# PCB_Curso_Octubre.net
KiCad netlist of a schematic drawn in Altium Designer
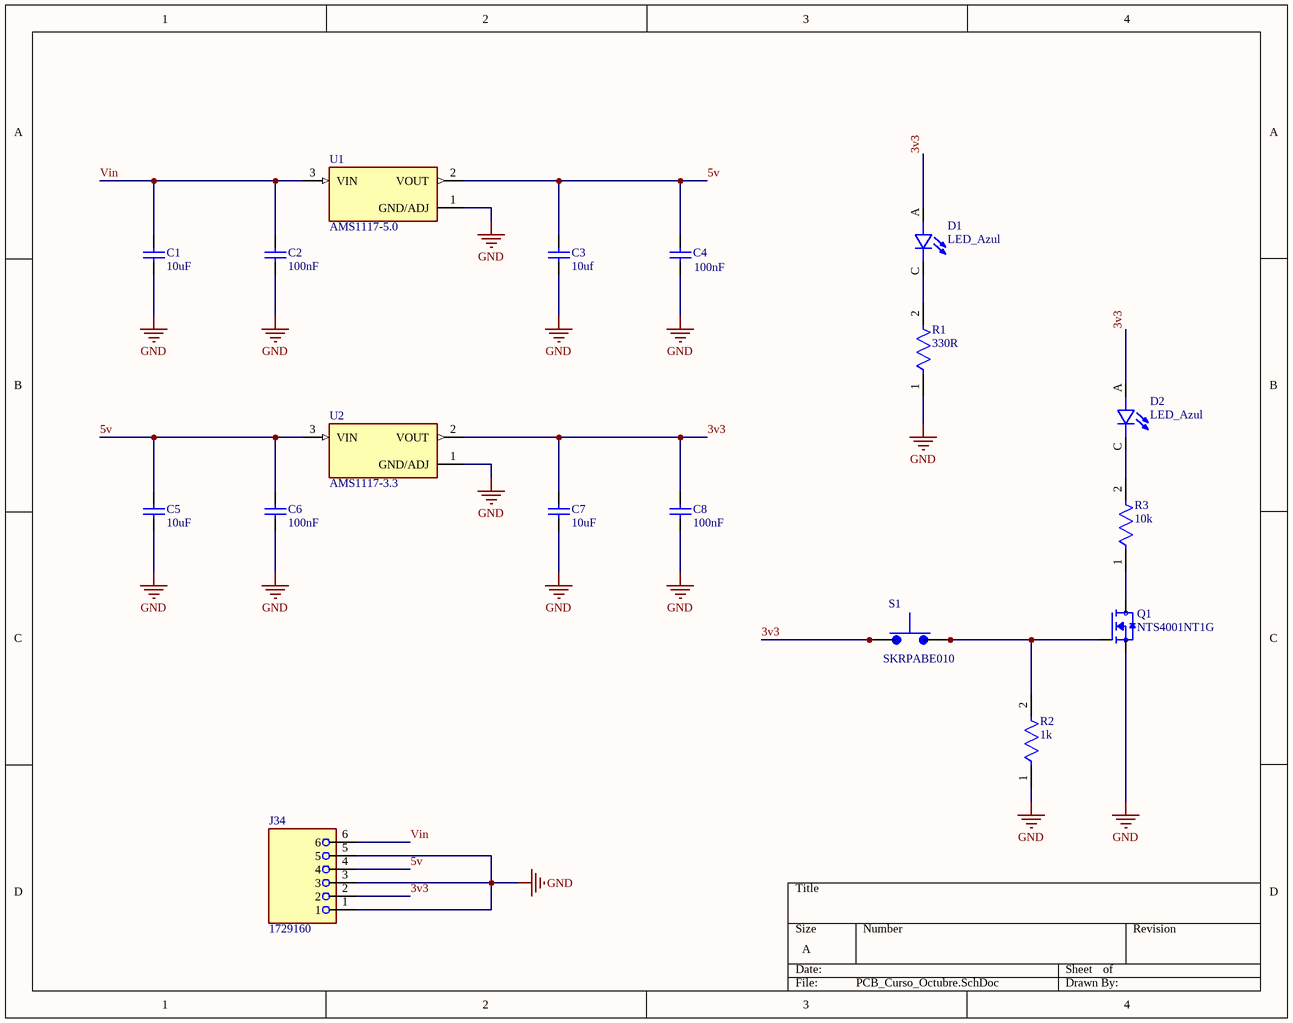
[diagram p0: PCB_Curso_Octubre.SchDoc]

(export (version "E")
  (design (tool "Eeschema 10.0.6"))
  (components
    (comp (ref "C1")
      (value "10uF")
      (footprint "CAPC2013X145X48ML20T23")
      (fields (field (name "MANUFACTURER") "Vitramon") (field (name "PART NUMBER") "VJ0805Y682KXAMT"))
      (libsource (lib "Altium Content Vault") (part "CAP"))
    )
    (comp (ref "C2")
      (value "100nF")
      (footprint "CAPC2013X145X48ML20T23")
      (fields (field (name "MANUFACTURER") "Vitramon") (field (name "PART NUMBER") "VJ0805Y682KXAMT"))
      (libsource (lib "Altium Content Vault") (part "CAP"))
    )
    (comp (ref "C3")
      (value "10uf")
      (footprint "CAPC2013X145X48ML20T23")
      (fields (field (name "MANUFACTURER") "Vitramon") (field (name "PART NUMBER") "VJ0805Y682KXAMT"))
      (libsource (lib "Altium Content Vault") (part "CAP"))
    )
    (comp (ref "C4")
      (value "100nF")
      (footprint "CAPC2013X145X48ML20T23")
      (fields (field (name "MANUFACTURER") "Vitramon") (field (name "PART NUMBER") "VJ0805Y682KXAMT"))
      (libsource (lib "Altium Content Vault") (part "CAP"))
    )
    (comp (ref "C5")
      (value "10uF")
      (footprint "CAPC2013X145X48ML20T23")
      (fields (field (name "MANUFACTURER") "Vitramon") (field (name "PART NUMBER") "VJ0805Y682KXAMT"))
      (libsource (lib "Altium Content Vault") (part "CAP"))
    )
    (comp (ref "C6")
      (value "100nF")
      (footprint "CAPC2013X145X48ML20T23")
      (fields (field (name "MANUFACTURER") "Vitramon") (field (name "PART NUMBER") "VJ0805Y682KXAMT"))
      (libsource (lib "Altium Content Vault") (part "CAP"))
    )
    (comp (ref "C7")
      (value "10uF")
      (footprint "CAPC2013X145X48ML20T23")
      (fields (field (name "MANUFACTURER") "Vitramon") (field (name "PART NUMBER") "VJ0805Y682KXAMT"))
      (libsource (lib "Altium Content Vault") (part "CAP"))
    )
    (comp (ref "C8")
      (value "100nF")
      (footprint "CAPC2013X145X48ML20T23")
      (fields (field (name "MANUFACTURER") "Vitramon") (field (name "PART NUMBER") "VJ0805Y682KXAMT"))
      (libsource (lib "Altium Content Vault") (part "CAP"))
    )
    (comp (ref "D1")
      (value "LED_Azul")
      (footprint "LEDC2012X120N")
      (fields (field (name "MF") "Lumex Opto/Components") (field (name "MP") "SML-LXT0805IW-TR"))
      (libsource (lib "SML-LXT0805IW-TR") (part "SML-LXT0805IW-TR"))
    )
    (comp (ref "D2")
      (value "LED_Azul")
      (footprint "LEDC2012X120N")
      (fields (field (name "MF") "Lumex Opto/Components") (field (name "MP") "SML-LXT0805IW-TR"))
      (libsource (lib "SML-LXT0805IW-TR") (part "SML-LXT0805IW-TR"))
    )
    (comp (ref "J34")
      (value "1729160")
      (footprint "PHOENIX_1729160")
      (fields (field (name "MF") "Phoenix Contact"))
      (libsource (lib "1729160") (part "1729160"))
    )
    (comp (ref "Q1")
      (value "NTS4001NT1G")
      (footprint "SOT65P220X100-3N")
      (description "N-Channel 30V 270mA _Ta_ 330mW _Ta_ Surface Mount SC-70-3 _SOT323_")
      (fields (field (name "MF") "ON Semiconductor"))
      (libsource (lib "NTS4001NT1G") (part "NTS4001NT1G"))
    )
    (comp (ref "R1")
      (value "330R")
      (footprint "FP-MCU0805-IPC_B")
      (description "RES 1.05K OHM 0.5% 1/5W 0805")
      (fields (field (name "TOLERANCE") "0.1%"))
      (libsource (lib "Altium Content Vault") (part "1029c3af85768c4190bb7ad29bc67b5"))
    )
    (comp (ref "R2")
      (value "1k")
      (footprint "FP-MCU0805-IPC_B")
      (description "RES 1.05K OHM 0.5% 1/5W 0805")
      (fields (field (name "TOLERANCE") "0.1%"))
      (libsource (lib "Altium Content Vault") (part "1029c3af85768c4190bb7ad29bc67b5"))
    )
    (comp (ref "R3")
      (value "10k")
      (footprint "FP-MCU0805-IPC_B")
      (description "RES 1.05K OHM 0.5% 1/5W 0805")
      (fields (field (name "TOLERANCE") "0.1%"))
      (libsource (lib "Altium Content Vault") (part "1029c3af85768c4190bb7ad29bc67b5"))
    )
    (comp (ref "S1")
      (value "SKRPABE010")
      (footprint "SW_SKRPABE010")
      (description "Switch Tactile N.O. SPST Button J-Bend 0.05A 16VDC 1.57N SMD Automotive T/R")
      (fields (field (name "MF") "ALPS"))
      (libsource (lib "SKRPABE010") (part "SKRPABE010"))
    )
    (comp (ref "U1")
      (value "AMS1117-5.0")
      (footprint "SOT229P700X180-4N")
      (description "1A LOW DROPOUT VOLTAGE REGULATOR")
      (fields (field (name "MF") "ams"))
      (libsource (lib "AMS1117-5v") (part "AMS1117-5.0"))
    )
    (comp (ref "U2")
      (value "AMS1117-3.3")
      (footprint "SOT229P700X180-4N")
      (description "1A LOW DROPOUT VOLTAGE REGULATOR")
      (fields (field (name "MP") "AMS1117-5.0") (field (name "MF") "ams"))
      (libsource (lib "AMS1117-3v3") (part "AMS1117-5.0"))
    )
  )
  (nets
    (net (code "1") (name "/3v3") (class "Default")
      (node (ref "C7") (pin "1") (pinfunction "1_1") (pintype "passive"))
      (node (ref "C8") (pin "1") (pinfunction "1_1") (pintype "passive"))
      (node (ref "D1") (pin "A") (pinfunction "A_A") (pintype "passive"))
      (node (ref "D2") (pin "A") (pinfunction "A_A") (pintype "passive"))
      (node (ref "J34") (pin "2") (pinfunction "2_2") (pintype "passive"))
      (node (ref "S1") (pin "1") (pinfunction "1_1") (pintype "passive"))
      (node (ref "S1") (pin "2") (pinfunction "1_2") (pintype "passive"))
      (node (ref "U2") (pin "2") (pinfunction "VOUT_2") (pintype "output"))
    )
    (net (code "2") (name "/5v") (class "Default")
      (node (ref "C3") (pin "1") (pinfunction "1_1") (pintype "passive"))
      (node (ref "C4") (pin "1") (pinfunction "1_1") (pintype "passive"))
      (node (ref "C5") (pin "1") (pinfunction "1_1") (pintype "passive"))
      (node (ref "C6") (pin "1") (pinfunction "1_1") (pintype "passive"))
      (node (ref "J34") (pin "4") (pinfunction "4_4") (pintype "passive"))
      (node (ref "U1") (pin "2") (pinfunction "VOUT_2") (pintype "output"))
      (node (ref "U2") (pin "3") (pinfunction "VIN_3") (pintype "input"))
    )
    (net (code "3") (name "/Vin") (class "Default")
      (node (ref "C1") (pin "1") (pinfunction "1_1") (pintype "passive"))
      (node (ref "C2") (pin "1") (pinfunction "1_1") (pintype "passive"))
      (node (ref "J34") (pin "6") (pinfunction "6_6") (pintype "passive"))
      (node (ref "U1") (pin "3") (pinfunction "VIN_3") (pintype "input"))
    )
    (net (code "4") (name "GND") (class "Default")
      (node (ref "C1") (pin "2") (pinfunction "2_2") (pintype "passive"))
      (node (ref "C2") (pin "2") (pinfunction "2_2") (pintype "passive"))
      (node (ref "C3") (pin "2") (pinfunction "2_2") (pintype "passive"))
      (node (ref "C4") (pin "2") (pinfunction "2_2") (pintype "passive"))
      (node (ref "C5") (pin "2") (pinfunction "2_2") (pintype "passive"))
      (node (ref "C6") (pin "2") (pinfunction "2_2") (pintype "passive"))
      (node (ref "C7") (pin "2") (pinfunction "2_2") (pintype "passive"))
      (node (ref "C8") (pin "2") (pinfunction "2_2") (pintype "passive"))
      (node (ref "J34") (pin "1") (pinfunction "1_1") (pintype "passive"))
      (node (ref "J34") (pin "3") (pinfunction "3_3") (pintype "passive"))
      (node (ref "J34") (pin "5") (pinfunction "5_5") (pintype "passive"))
      (node (ref "Q1") (pin "2") (pinfunction "S_2") (pintype "passive"))
      (node (ref "R1") (pin "1") (pinfunction "1_1") (pintype "passive"))
      (node (ref "R2") (pin "1") (pinfunction "1_1") (pintype "passive"))
      (node (ref "U1") (pin "1") (pinfunction "GND/ADJ_1") (pintype "power_in"))
      (node (ref "U2") (pin "1") (pinfunction "GND/ADJ_1") (pintype "power_in"))
    )
    (net (code "5") (name "Net-(D1-PadC)") (class "Default")
      (node (ref "D1") (pin "C") (pinfunction "C_C") (pintype "passive"))
      (node (ref "R1") (pin "2") (pinfunction "2_2") (pintype "passive"))
    )
    (net (code "6") (name "Net-(D2-PadC)") (class "Default")
      (node (ref "D2") (pin "C") (pinfunction "C_C") (pintype "passive"))
      (node (ref "R3") (pin "2") (pinfunction "2_2") (pintype "passive"))
    )
    (net (code "7") (name "Net-(Q1-D)") (class "Default")
      (node (ref "Q1") (pin "3") (pinfunction "D_3") (pintype "passive"))
      (node (ref "R3") (pin "1") (pinfunction "1_1") (pintype "passive"))
    )
    (net (code "8") (name "Net-(Q1-G)") (class "Default")
      (node (ref "Q1") (pin "1") (pinfunction "G_1") (pintype "passive"))
      (node (ref "R2") (pin "2") (pinfunction "2_2") (pintype "passive"))
      (node (ref "S1") (pin "3") (pinfunction "2_3") (pintype "passive"))
      (node (ref "S1") (pin "4") (pinfunction "2_4") (pintype "passive"))
    )
  )
)
